# design.net
KiCad netlist of a schematic drawn in EasyEDA Pro
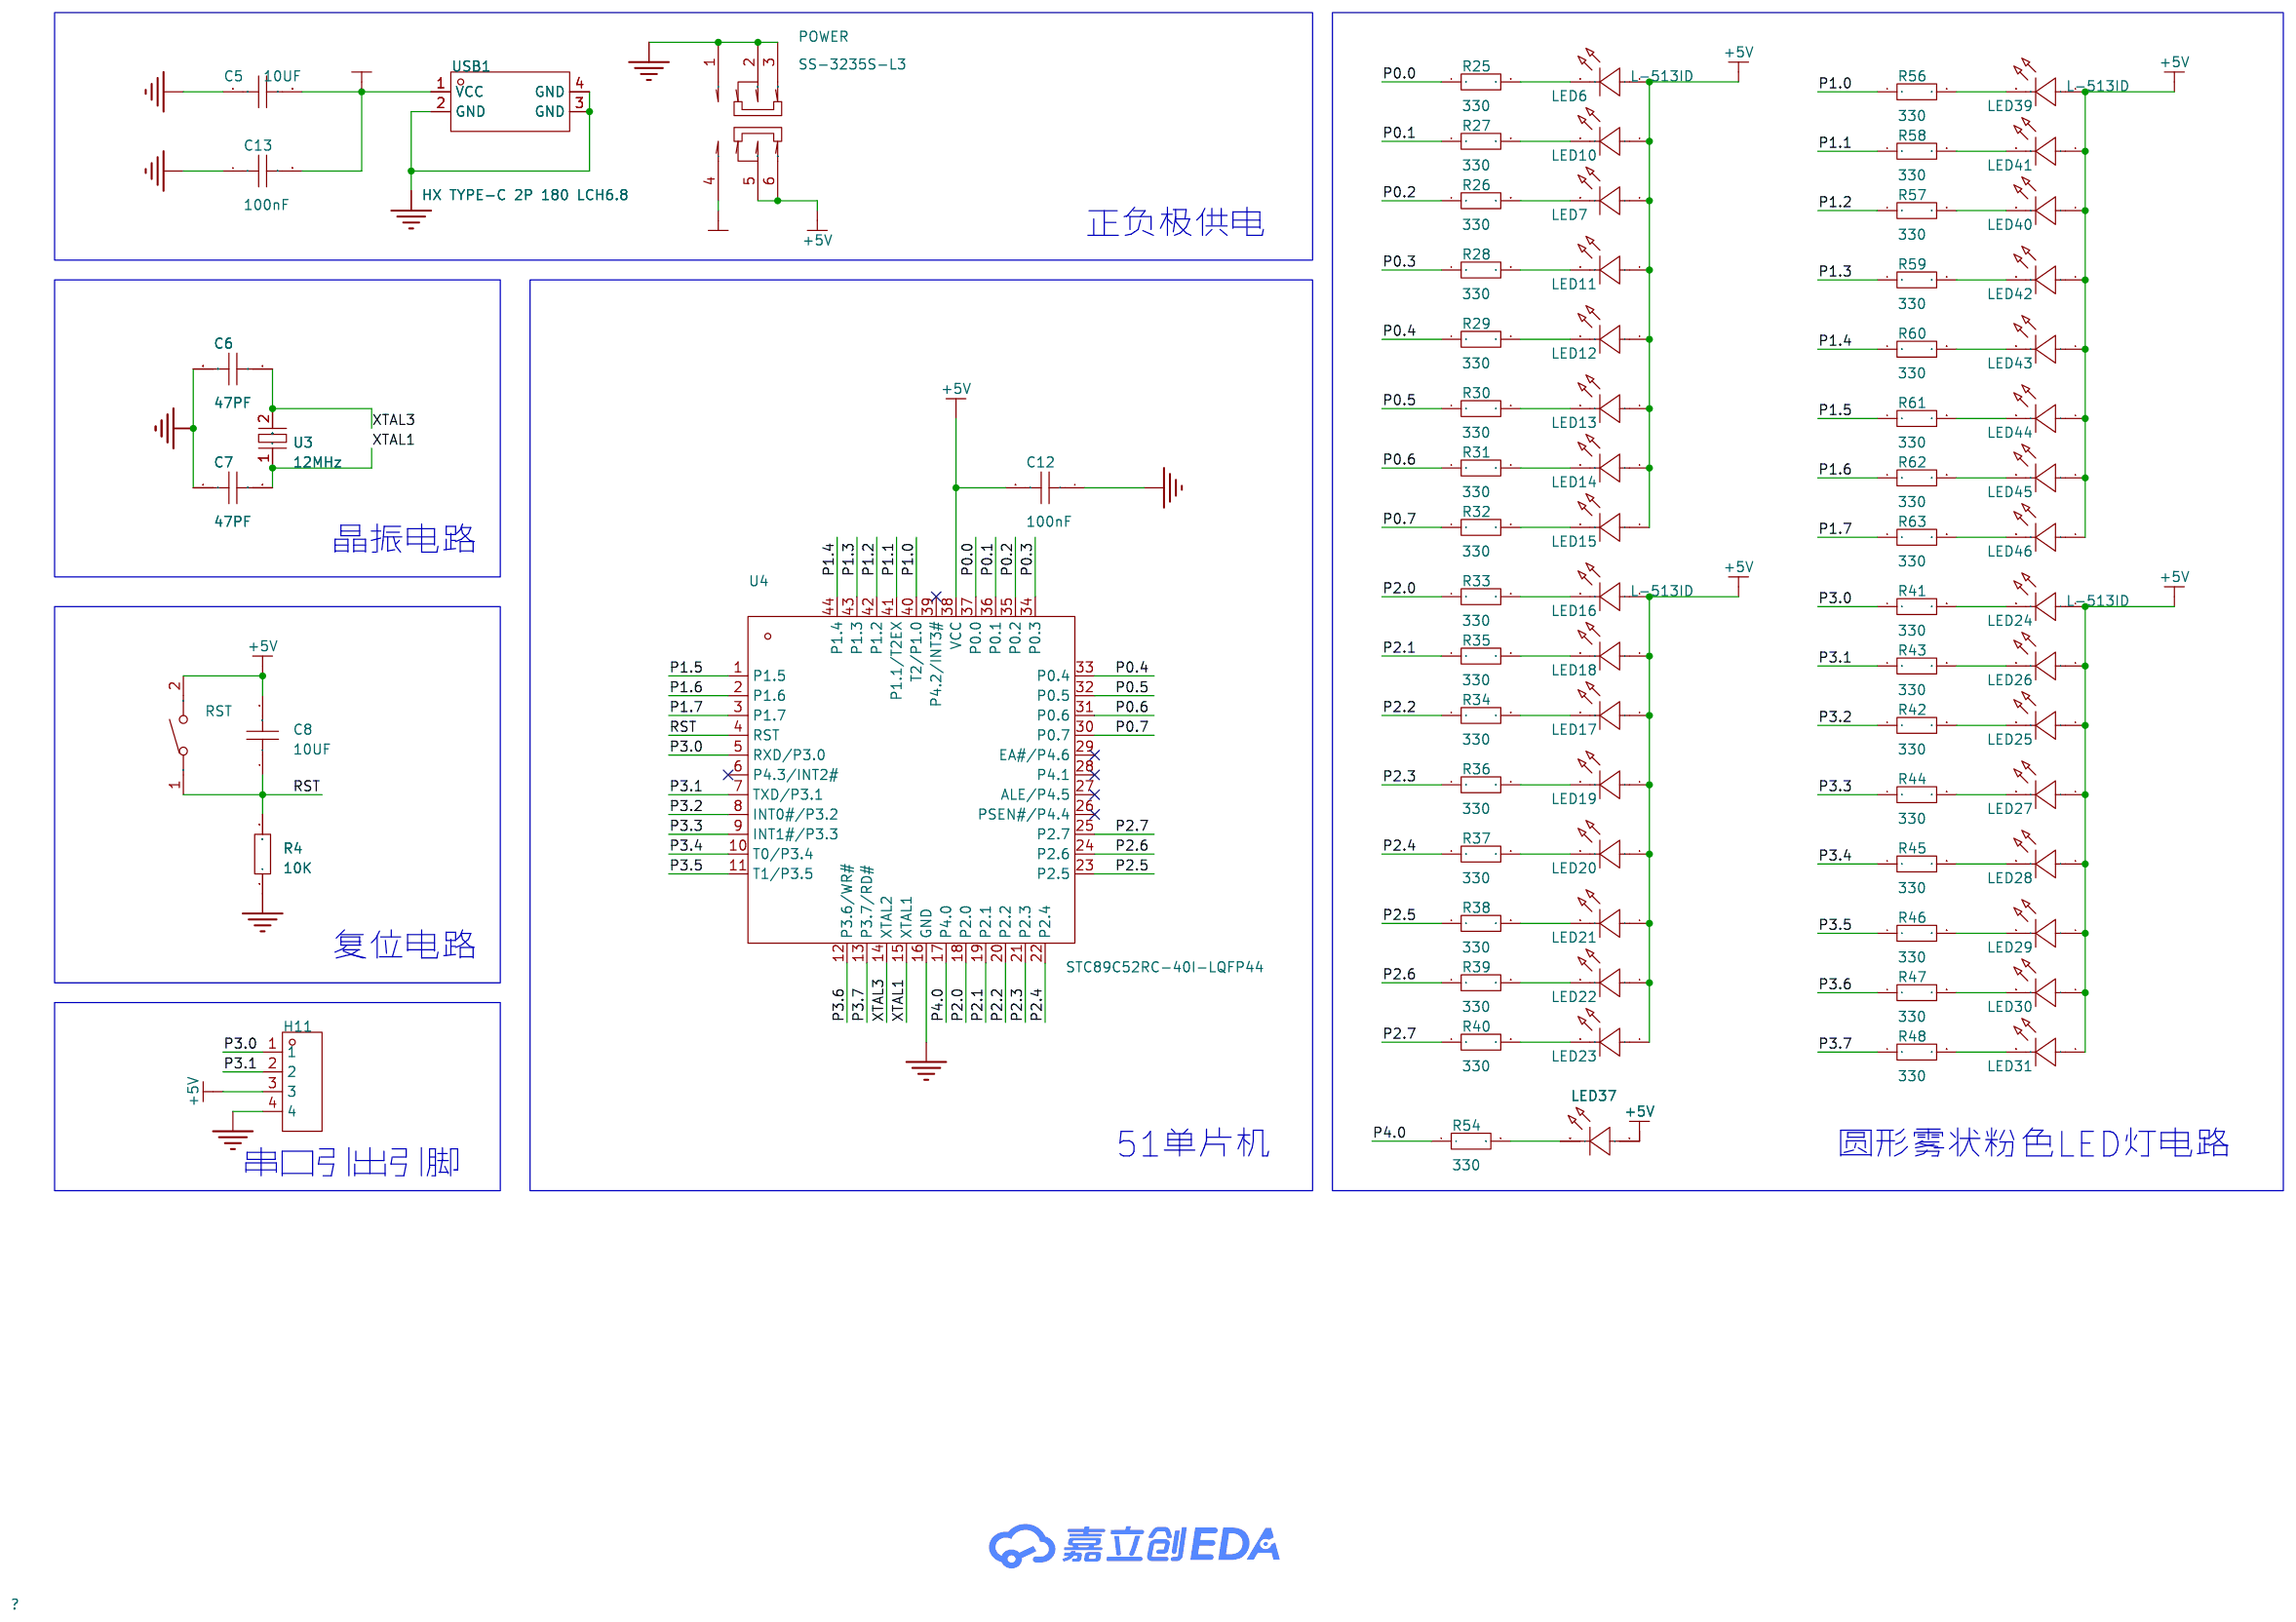
[diagram p0: schematic sheet]

(export (version "E")
  (design (tool "Eeschema 10.0.6"))
  (components
    (comp (ref "C5")
      (value "10UF")
      (footprint "easyedapro:C0805")
      (libsource (lib "easyedapro") (part "CapAcitance"))
    )
    (comp (ref "C6")
      (value "47PF")
      (footprint "easyedapro:C0805")
      (libsource (lib "easyedapro") (part "CapAcitance"))
    )
    (comp (ref "C7")
      (value "47PF")
      (footprint "easyedapro:C0805")
      (libsource (lib "easyedapro") (part "CapAcitance"))
    )
    (comp (ref "C8")
      (value "10UF")
      (footprint "easyedapro:C0805")
      (libsource (lib "easyedapro") (part "CapAcitance"))
    )
    (comp (ref "C12")
      (value "100nF")
      (footprint "easyedapro:C0805")
      (libsource (lib "easyedapro") (part "CapAcitance"))
    )
    (comp (ref "C13")
      (value "100nF")
      (footprint "easyedapro:C0805")
      (libsource (lib "easyedapro") (part "CapAcitance"))
    )
    (comp (ref "H11")
      (value "~")
      (footprint "easyedapro:HDR-TH_4P-P2.54-V-M")
      (libsource (lib "easyedapro") (part "PZ254V-11-04P"))
    )
    (comp (ref "LED6")
      (value "L-513ID")
      (footprint "easyedapro:LED-TH_BD5.9-P2.54-FD-1")
      (fields (field (name "Manufacturer") "PARALIGHT(光鼎)"))
      (libsource (lib "easyedapro") (part "L-513ID"))
    )
    (comp (ref "LED7")
      (value "L-513ID")
      (footprint "easyedapro:LED-TH_BD5.9-P2.54-FD-1")
      (fields (field (name "Manufacturer") "PARALIGHT(光鼎)"))
      (libsource (lib "easyedapro") (part "L-513ID"))
    )
    (comp (ref "LED10")
      (value "L-513ID")
      (footprint "easyedapro:LED-TH_BD5.9-P2.54-FD-1")
      (fields (field (name "Manufacturer") "PARALIGHT(光鼎)"))
      (libsource (lib "easyedapro") (part "L-513ID"))
    )
    (comp (ref "LED11")
      (value "L-513ID")
      (footprint "easyedapro:LED-TH_BD5.9-P2.54-FD-1")
      (fields (field (name "Manufacturer") "PARALIGHT(光鼎)"))
      (libsource (lib "easyedapro") (part "L-513ID"))
    )
    (comp (ref "LED12")
      (value "L-513ID")
      (footprint "easyedapro:LED-TH_BD5.9-P2.54-FD-1")
      (fields (field (name "Manufacturer") "PARALIGHT(光鼎)"))
      (libsource (lib "easyedapro") (part "L-513ID"))
    )
    (comp (ref "LED13")
      (value "L-513ID")
      (footprint "easyedapro:LED-TH_BD5.9-P2.54-FD-1")
      (fields (field (name "Manufacturer") "PARALIGHT(光鼎)"))
      (libsource (lib "easyedapro") (part "L-513ID"))
    )
    (comp (ref "LED14")
      (value "L-513ID")
      (footprint "easyedapro:LED-TH_BD5.9-P2.54-FD-1")
      (fields (field (name "Manufacturer") "PARALIGHT(光鼎)"))
      (libsource (lib "easyedapro") (part "L-513ID"))
    )
    (comp (ref "LED15")
      (value "L-513ID")
      (footprint "easyedapro:LED-TH_BD5.9-P2.54-FD-1")
      (fields (field (name "Manufacturer") "PARALIGHT(光鼎)"))
      (libsource (lib "easyedapro") (part "L-513ID"))
    )
    (comp (ref "LED16")
      (value "L-513ID")
      (footprint "easyedapro:LED-TH_BD5.9-P2.54-FD-1")
      (fields (field (name "Manufacturer") "PARALIGHT(光鼎)"))
      (libsource (lib "easyedapro") (part "L-513ID"))
    )
    (comp (ref "LED17")
      (value "L-513ID")
      (footprint "easyedapro:LED-TH_BD5.9-P2.54-FD-1")
      (fields (field (name "Manufacturer") "PARALIGHT(光鼎)"))
      (libsource (lib "easyedapro") (part "L-513ID"))
    )
    (comp (ref "LED18")
      (value "L-513ID")
      (footprint "easyedapro:LED-TH_BD5.9-P2.54-FD-1")
      (fields (field (name "Manufacturer") "PARALIGHT(光鼎)"))
      (libsource (lib "easyedapro") (part "L-513ID"))
    )
    (comp (ref "LED19")
      (value "L-513ID")
      (footprint "easyedapro:LED-TH_BD5.9-P2.54-FD-1")
      (fields (field (name "Manufacturer") "PARALIGHT(光鼎)"))
      (libsource (lib "easyedapro") (part "L-513ID"))
    )
    (comp (ref "LED20")
      (value "L-513ID")
      (footprint "easyedapro:LED-TH_BD5.9-P2.54-FD-1")
      (fields (field (name "Manufacturer") "PARALIGHT(光鼎)"))
      (libsource (lib "easyedapro") (part "L-513ID"))
    )
    (comp (ref "LED21")
      (value "L-513ID")
      (footprint "easyedapro:LED-TH_BD5.9-P2.54-FD-1")
      (fields (field (name "Manufacturer") "PARALIGHT(光鼎)"))
      (libsource (lib "easyedapro") (part "L-513ID"))
    )
    (comp (ref "LED22")
      (value "L-513ID")
      (footprint "easyedapro:LED-TH_BD5.9-P2.54-FD-1")
      (fields (field (name "Manufacturer") "PARALIGHT(光鼎)"))
      (libsource (lib "easyedapro") (part "L-513ID"))
    )
    (comp (ref "LED23")
      (value "L-513ID")
      (footprint "easyedapro:LED-TH_BD5.9-P2.54-FD-1")
      (fields (field (name "Manufacturer") "PARALIGHT(光鼎)"))
      (libsource (lib "easyedapro") (part "L-513ID"))
    )
    (comp (ref "LED24")
      (value "L-513ID")
      (footprint "easyedapro:LED-TH_BD5.9-P2.54-FD-1")
      (fields (field (name "Manufacturer") "PARALIGHT(光鼎)"))
      (libsource (lib "easyedapro") (part "L-513ID"))
    )
    (comp (ref "LED25")
      (value "L-513ID")
      (footprint "easyedapro:LED-TH_BD5.9-P2.54-FD-1")
      (fields (field (name "Manufacturer") "PARALIGHT(光鼎)"))
      (libsource (lib "easyedapro") (part "L-513ID"))
    )
    (comp (ref "LED26")
      (value "L-513ID")
      (footprint "easyedapro:LED-TH_BD5.9-P2.54-FD-1")
      (fields (field (name "Manufacturer") "PARALIGHT(光鼎)"))
      (libsource (lib "easyedapro") (part "L-513ID"))
    )
    (comp (ref "LED27")
      (value "L-513ID")
      (footprint "easyedapro:LED-TH_BD5.9-P2.54-FD-1")
      (fields (field (name "Manufacturer") "PARALIGHT(光鼎)"))
      (libsource (lib "easyedapro") (part "L-513ID"))
    )
    (comp (ref "LED28")
      (value "L-513ID")
      (footprint "easyedapro:LED-TH_BD5.9-P2.54-FD-1")
      (fields (field (name "Manufacturer") "PARALIGHT(光鼎)"))
      (libsource (lib "easyedapro") (part "L-513ID"))
    )
    (comp (ref "LED29")
      (value "L-513ID")
      (footprint "easyedapro:LED-TH_BD5.9-P2.54-FD-1")
      (fields (field (name "Manufacturer") "PARALIGHT(光鼎)"))
      (libsource (lib "easyedapro") (part "L-513ID"))
    )
    (comp (ref "LED30")
      (value "L-513ID")
      (footprint "easyedapro:LED-TH_BD5.9-P2.54-FD-1")
      (fields (field (name "Manufacturer") "PARALIGHT(光鼎)"))
      (libsource (lib "easyedapro") (part "L-513ID"))
    )
    (comp (ref "LED31")
      (value "L-513ID")
      (footprint "easyedapro:LED-TH_BD5.9-P2.54-FD-1")
      (fields (field (name "Manufacturer") "PARALIGHT(光鼎)"))
      (libsource (lib "easyedapro") (part "L-513ID"))
    )
    (comp (ref "LED37")
      (value "L-513ID")
      (footprint "easyedapro:LED-TH_BD5.9-P2.54-FD-1")
      (fields (field (name "Manufacturer") "PARALIGHT(光鼎)"))
      (libsource (lib "easyedapro") (part "L-513ID"))
    )
    (comp (ref "LED39")
      (value "L-513ID")
      (footprint "easyedapro:LED-TH_BD5.9-P2.54-FD-1")
      (fields (field (name "Manufacturer") "PARALIGHT(光鼎)"))
      (libsource (lib "easyedapro") (part "L-513ID"))
    )
    (comp (ref "LED40")
      (value "L-513ID")
      (footprint "easyedapro:LED-TH_BD5.9-P2.54-FD-1")
      (fields (field (name "Manufacturer") "PARALIGHT(光鼎)"))
      (libsource (lib "easyedapro") (part "L-513ID"))
    )
    (comp (ref "LED41")
      (value "L-513ID")
      (footprint "easyedapro:LED-TH_BD5.9-P2.54-FD-1")
      (fields (field (name "Manufacturer") "PARALIGHT(光鼎)"))
      (libsource (lib "easyedapro") (part "L-513ID"))
    )
    (comp (ref "LED42")
      (value "L-513ID")
      (footprint "easyedapro:LED-TH_BD5.9-P2.54-FD-1")
      (fields (field (name "Manufacturer") "PARALIGHT(光鼎)"))
      (libsource (lib "easyedapro") (part "L-513ID"))
    )
    (comp (ref "LED43")
      (value "L-513ID")
      (footprint "easyedapro:LED-TH_BD5.9-P2.54-FD-1")
      (fields (field (name "Manufacturer") "PARALIGHT(光鼎)"))
      (libsource (lib "easyedapro") (part "L-513ID"))
    )
    (comp (ref "LED44")
      (value "L-513ID")
      (footprint "easyedapro:LED-TH_BD5.9-P2.54-FD-1")
      (fields (field (name "Manufacturer") "PARALIGHT(光鼎)"))
      (libsource (lib "easyedapro") (part "L-513ID"))
    )
    (comp (ref "LED45")
      (value "L-513ID")
      (footprint "easyedapro:LED-TH_BD5.9-P2.54-FD-1")
      (fields (field (name "Manufacturer") "PARALIGHT(光鼎)"))
      (libsource (lib "easyedapro") (part "L-513ID"))
    )
    (comp (ref "LED46")
      (value "L-513ID")
      (footprint "easyedapro:LED-TH_BD5.9-P2.54-FD-1")
      (fields (field (name "Manufacturer") "PARALIGHT(光鼎)"))
      (libsource (lib "easyedapro") (part "L-513ID"))
    )
    (comp (ref "POWER")
      (value "SS-3235S-L3")
      (footprint "easyedapro:SW-SMD_SS-3235S-L3.00")
      (description "电路结构:双刀双掷;安装方式:立贴;开关颜色:黑色;额定电流(DC):50mA;额定电压(DC):12V;额定电流(AC):50mA;额定电压(AC):12V;机械寿命:1万次;")
      (fields (field (name "Manufacturer") "XKB Connectivity(中国星坤)"))
      (libsource (lib "easyedapro") (part "SS-3235S-L3"))
    )
    (comp (ref "R4") (value "10K") (footprint "easyedapro:R0805") (libsource (lib "easyedapro") (part "电阻")))
    (comp (ref "R25") (value "330") (footprint "easyedapro:R0805") (libsource (lib "easyedapro") (part "电阻")))
    (comp (ref "R26") (value "330") (footprint "easyedapro:R0805") (libsource (lib "easyedapro") (part "电阻")))
    (comp (ref "R27") (value "330") (footprint "easyedapro:R0805") (libsource (lib "easyedapro") (part "电阻")))
    (comp (ref "R28") (value "330") (footprint "easyedapro:R0805") (libsource (lib "easyedapro") (part "电阻")))
    (comp (ref "R29") (value "330") (footprint "easyedapro:R0805") (libsource (lib "easyedapro") (part "电阻")))
    (comp (ref "R30") (value "330") (footprint "easyedapro:R0805") (libsource (lib "easyedapro") (part "电阻")))
    (comp (ref "R31") (value "330") (footprint "easyedapro:R0805") (libsource (lib "easyedapro") (part "电阻")))
    (comp (ref "R32") (value "330") (footprint "easyedapro:R0805") (libsource (lib "easyedapro") (part "电阻")))
    (comp (ref "R33") (value "330") (footprint "easyedapro:R0805") (libsource (lib "easyedapro") (part "电阻")))
    (comp (ref "R34") (value "330") (footprint "easyedapro:R0805") (libsource (lib "easyedapro") (part "电阻")))
    (comp (ref "R35") (value "330") (footprint "easyedapro:R0805") (libsource (lib "easyedapro") (part "电阻")))
    (comp (ref "R36") (value "330") (footprint "easyedapro:R0805") (libsource (lib "easyedapro") (part "电阻")))
    (comp (ref "R37") (value "330") (footprint "easyedapro:R0805") (libsource (lib "easyedapro") (part "电阻")))
    (comp (ref "R38") (value "330") (footprint "easyedapro:R0805") (libsource (lib "easyedapro") (part "电阻")))
    (comp (ref "R39") (value "330") (footprint "easyedapro:R0805") (libsource (lib "easyedapro") (part "电阻")))
    (comp (ref "R40") (value "330") (footprint "easyedapro:R0805") (libsource (lib "easyedapro") (part "电阻")))
    (comp (ref "R41") (value "330") (footprint "easyedapro:R0805") (libsource (lib "easyedapro") (part "电阻")))
    (comp (ref "R42") (value "330") (footprint "easyedapro:R0805") (libsource (lib "easyedapro") (part "电阻")))
    (comp (ref "R43") (value "330") (footprint "easyedapro:R0805") (libsource (lib "easyedapro") (part "电阻")))
    (comp (ref "R44") (value "330") (footprint "easyedapro:R0805") (libsource (lib "easyedapro") (part "电阻")))
    (comp (ref "R45") (value "330") (footprint "easyedapro:R0805") (libsource (lib "easyedapro") (part "电阻")))
    (comp (ref "R46") (value "330") (footprint "easyedapro:R0805") (libsource (lib "easyedapro") (part "电阻")))
    (comp (ref "R47") (value "330") (footprint "easyedapro:R0805") (libsource (lib "easyedapro") (part "电阻")))
    (comp (ref "R48") (value "330") (footprint "easyedapro:R0805") (libsource (lib "easyedapro") (part "电阻")))
    (comp (ref "R54") (value "330") (footprint "easyedapro:R0805") (libsource (lib "easyedapro") (part "电阻")))
    (comp (ref "R56") (value "330") (footprint "easyedapro:R0805") (libsource (lib "easyedapro") (part "电阻")))
    (comp (ref "R57") (value "330") (footprint "easyedapro:R0805") (libsource (lib "easyedapro") (part "电阻")))
    (comp (ref "R58") (value "330") (footprint "easyedapro:R0805") (libsource (lib "easyedapro") (part "电阻")))
    (comp (ref "R59") (value "330") (footprint "easyedapro:R0805") (libsource (lib "easyedapro") (part "电阻")))
    (comp (ref "R60") (value "330") (footprint "easyedapro:R0805") (libsource (lib "easyedapro") (part "电阻")))
    (comp (ref "R61") (value "330") (footprint "easyedapro:R0805") (libsource (lib "easyedapro") (part "电阻")))
    (comp (ref "R62") (value "330") (footprint "easyedapro:R0805") (libsource (lib "easyedapro") (part "电阻")))
    (comp (ref "R63") (value "330") (footprint "easyedapro:R0805") (libsource (lib "easyedapro") (part "电阻")))
    (comp (ref "RST")
      (value "轻触按键3*4*H")
      (footprint "easyedapro:SW-SMD_L4.0-W2.9-LS5.0")
      (libsource (lib "easyedapro") (part "轻触按键3*4*H"))
    )
    (comp (ref "U3")
      (value "12MHz")
      (footprint "easyedapro:CRYSTAL-SMD_L11.4-W4.7-LS12.7")
      (description "频率:12MHz;常温频差:±30ppm;外接负载电容:18pF;频率稳定度(全温):±35ppm;")
      (fields
        (field (name "Manufacturer Part") "ABLS-12.000MHZ-B4H-T")
        (field (name "Manufacturer") "ABRACON")
      )
      (libsource (lib "easyedapro") (part "ABLS-12.000MHZ-B4H-T"))
    )
    (comp (ref "U4")
      (value "STC89C52RC-40I-LQFP44")
      (footprint "easyedapro:LQFP-44_L10.0-W10.0-P0.80-LS12.0-BL")
      (description "CPU内核:51系列;应用领域:-;")
      (fields (field (name "Manufacturer") "STC"))
      (libsource (lib "easyedapro") (part "STC89C52RC-40I_C8707"))
    )
    (comp (ref "USB1")
      (value "HX TYPE-C 2P 180 LCH6.8")
      (footprint "easyedapro:USB-TH_HX-TYPE-C-2P-180-LCH6.8")
      (description "连接器类型:Type-C;标准:-;公母:母;安装方式:直插;触点数量:2P;端口数量:1;额定电流 - 电源:3A;工作温度范围:-30°C~+80°C;")
      (fields (field (name "Manufacturer") "hanxia(韩下)"))
      (libsource (lib "easyedapro") (part "HX TYPE-C 2P 180 LCH6.8"))
    )
  )
  (nets
    (net (code "1") (name "+5V") (class "Default")
      (node (ref "C12") (pin "2") (pinfunction "2_2") (pintype "input"))
      (node (ref "C8") (pin "2") (pinfunction "2_2") (pintype "input"))
      (node (ref "H11") (pin "3") (pinfunction "3_3") (pintype "unspecified"))
      (node (ref "LED10") (pin "1") (pinfunction "A_1") (pintype "unspecified"))
      (node (ref "LED11") (pin "1") (pinfunction "A_1") (pintype "unspecified"))
      (node (ref "LED12") (pin "1") (pinfunction "A_1") (pintype "unspecified"))
      (node (ref "LED13") (pin "1") (pinfunction "A_1") (pintype "unspecified"))
      (node (ref "LED14") (pin "1") (pinfunction "A_1") (pintype "unspecified"))
      (node (ref "LED15") (pin "1") (pinfunction "A_1") (pintype "unspecified"))
      (node (ref "LED16") (pin "1") (pinfunction "A_1") (pintype "unspecified"))
      (node (ref "LED17") (pin "1") (pinfunction "A_1") (pintype "unspecified"))
      (node (ref "LED18") (pin "1") (pinfunction "A_1") (pintype "unspecified"))
      (node (ref "LED19") (pin "1") (pinfunction "A_1") (pintype "unspecified"))
      (node (ref "LED20") (pin "1") (pinfunction "A_1") (pintype "unspecified"))
      (node (ref "LED21") (pin "1") (pinfunction "A_1") (pintype "unspecified"))
      (node (ref "LED22") (pin "1") (pinfunction "A_1") (pintype "unspecified"))
      (node (ref "LED23") (pin "1") (pinfunction "A_1") (pintype "unspecified"))
      (node (ref "LED24") (pin "1") (pinfunction "A_1") (pintype "unspecified"))
      (node (ref "LED25") (pin "1") (pinfunction "A_1") (pintype "unspecified"))
      (node (ref "LED26") (pin "1") (pinfunction "A_1") (pintype "unspecified"))
      (node (ref "LED27") (pin "1") (pinfunction "A_1") (pintype "unspecified"))
      (node (ref "LED28") (pin "1") (pinfunction "A_1") (pintype "unspecified"))
      (node (ref "LED29") (pin "1") (pinfunction "A_1") (pintype "unspecified"))
      (node (ref "LED30") (pin "1") (pinfunction "A_1") (pintype "unspecified"))
      (node (ref "LED31") (pin "1") (pinfunction "A_1") (pintype "unspecified"))
      (node (ref "LED37") (pin "1") (pinfunction "A_1") (pintype "unspecified"))
      (node (ref "LED39") (pin "1") (pinfunction "A_1") (pintype "unspecified"))
      (node (ref "LED40") (pin "1") (pinfunction "A_1") (pintype "unspecified"))
      (node (ref "LED41") (pin "1") (pinfunction "A_1") (pintype "unspecified"))
      (node (ref "LED42") (pin "1") (pinfunction "A_1") (pintype "unspecified"))
      (node (ref "LED43") (pin "1") (pinfunction "A_1") (pintype "unspecified"))
      (node (ref "LED44") (pin "1") (pinfunction "A_1") (pintype "unspecified"))
      (node (ref "LED45") (pin "1") (pinfunction "A_1") (pintype "unspecified"))
      (node (ref "LED46") (pin "1") (pinfunction "A_1") (pintype "unspecified"))
      (node (ref "LED6") (pin "1") (pinfunction "A_1") (pintype "unspecified"))
      (node (ref "LED7") (pin "1") (pinfunction "A_1") (pintype "unspecified"))
      (node (ref "POWER") (pin "5") (pinfunction "5_5") (pintype "unspecified"))
      (node (ref "POWER") (pin "6") (pinfunction "6_6") (pintype "unspecified"))
      (node (ref "RST") (pin "2") (pinfunction "2_2") (pintype "unspecified"))
      (node (ref "U4") (pin "38") (pinfunction "VCC_38") (pintype "unspecified"))
    )
    (net (code "2") (name "/P0.0") (class "Default")
      (node (ref "R25") (pin "1") (pinfunction "1_1") (pintype "input"))
      (node (ref "U4") (pin "37") (pinfunction "P0.0_37") (pintype "unspecified"))
    )
    (net (code "3") (name "/P0.1") (class "Default")
      (node (ref "R27") (pin "1") (pinfunction "1_1") (pintype "input"))
      (node (ref "U4") (pin "36") (pinfunction "P0.1_36") (pintype "unspecified"))
    )
    (net (code "4") (name "/P0.2") (class "Default")
      (node (ref "R26") (pin "1") (pinfunction "1_1") (pintype "input"))
      (node (ref "U4") (pin "35") (pinfunction "P0.2_35") (pintype "unspecified"))
    )
    (net (code "5") (name "/P0.3") (class "Default")
      (node (ref "R28") (pin "1") (pinfunction "1_1") (pintype "input"))
      (node (ref "U4") (pin "34") (pinfunction "P0.3_34") (pintype "unspecified"))
    )
    (net (code "6") (name "/P0.4") (class "Default")
      (node (ref "R29") (pin "1") (pinfunction "1_1") (pintype "input"))
      (node (ref "U4") (pin "33") (pinfunction "P0.4_33") (pintype "unspecified"))
    )
    (net (code "7") (name "/P0.5") (class "Default")
      (node (ref "R30") (pin "1") (pinfunction "1_1") (pintype "input"))
      (node (ref "U4") (pin "32") (pinfunction "P0.5_32") (pintype "unspecified"))
    )
    (net (code "8") (name "/P0.6") (class "Default")
      (node (ref "R31") (pin "1") (pinfunction "1_1") (pintype "input"))
      (node (ref "U4") (pin "31") (pinfunction "P0.6_31") (pintype "unspecified"))
    )
    (net (code "9") (name "/P0.7") (class "Default")
      (node (ref "R32") (pin "1") (pinfunction "1_1") (pintype "input"))
      (node (ref "U4") (pin "30") (pinfunction "P0.7_30") (pintype "unspecified"))
    )
    (net (code "10") (name "/P1.0") (class "Default")
      (node (ref "R56") (pin "1") (pinfunction "1_1") (pintype "input"))
      (node (ref "U4") (pin "40") (pinfunction "T2/P1.0_40") (pintype "unspecified"))
    )
    (net (code "11") (name "/P1.1") (class "Default")
      (node (ref "R58") (pin "1") (pinfunction "1_1") (pintype "input"))
      (node (ref "U4") (pin "41") (pinfunction "P1.1/T2EX_41") (pintype "unspecified"))
    )
    (net (code "12") (name "/P1.2") (class "Default")
      (node (ref "R57") (pin "1") (pinfunction "1_1") (pintype "input"))
      (node (ref "U4") (pin "42") (pinfunction "P1.2_42") (pintype "unspecified"))
    )
    (net (code "13") (name "/P1.3") (class "Default")
      (node (ref "R59") (pin "1") (pinfunction "1_1") (pintype "input"))
      (node (ref "U4") (pin "43") (pinfunction "P1.3_43") (pintype "unspecified"))
    )
    (net (code "14") (name "/P1.4") (class "Default")
      (node (ref "R60") (pin "1") (pinfunction "1_1") (pintype "input"))
      (node (ref "U4") (pin "44") (pinfunction "P1.4_44") (pintype "unspecified"))
    )
    (net (code "15") (name "/P1.5") (class "Default")
      (node (ref "R61") (pin "1") (pinfunction "1_1") (pintype "input"))
      (node (ref "U4") (pin "1") (pinfunction "P1.5_1") (pintype "unspecified"))
    )
    (net (code "16") (name "/P1.6") (class "Default")
      (node (ref "R62") (pin "1") (pinfunction "1_1") (pintype "input"))
      (node (ref "U4") (pin "2") (pinfunction "P1.6_2") (pintype "unspecified"))
    )
    (net (code "17") (name "/P1.7") (class "Default")
      (node (ref "R63") (pin "1") (pinfunction "1_1") (pintype "input"))
      (node (ref "U4") (pin "3") (pinfunction "P1.7_3") (pintype "unspecified"))
    )
    (net (code "18") (name "/P2.0") (class "Default")
      (node (ref "R33") (pin "1") (pinfunction "1_1") (pintype "input"))
      (node (ref "U4") (pin "18") (pinfunction "P2.0_18") (pintype "unspecified"))
    )
    (net (code "19") (name "/P2.1") (class "Default")
      (node (ref "R35") (pin "1") (pinfunction "1_1") (pintype "input"))
      (node (ref "U4") (pin "19") (pinfunction "P2.1_19") (pintype "unspecified"))
    )
    (net (code "20") (name "/P2.2") (class "Default")
      (node (ref "R34") (pin "1") (pinfunction "1_1") (pintype "input"))
      (node (ref "U4") (pin "20") (pinfunction "P2.2_20") (pintype "unspecified"))
    )
    (net (code "21") (name "/P2.3") (class "Default")
      (node (ref "R36") (pin "1") (pinfunction "1_1") (pintype "input"))
      (node (ref "U4") (pin "21") (pinfunction "P2.3_21") (pintype "unspecified"))
    )
    (net (code "22") (name "/P2.4") (class "Default")
      (node (ref "R37") (pin "1") (pinfunction "1_1") (pintype "input"))
      (node (ref "U4") (pin "22") (pinfunction "P2.4_22") (pintype "unspecified"))
    )
    (net (code "23") (name "/P2.5") (class "Default")
      (node (ref "R38") (pin "1") (pinfunction "1_1") (pintype "input"))
      (node (ref "U4") (pin "23") (pinfunction "P2.5_23") (pintype "unspecified"))
    )
    (net (code "24") (name "/P2.6") (class "Default")
      (node (ref "R39") (pin "1") (pinfunction "1_1") (pintype "input"))
      (node (ref "U4") (pin "24") (pinfunction "P2.6_24") (pintype "unspecified"))
    )
    (net (code "25") (name "/P2.7") (class "Default")
      (node (ref "R40") (pin "1") (pinfunction "1_1") (pintype "input"))
      (node (ref "U4") (pin "25") (pinfunction "P2.7_25") (pintype "unspecified"))
    )
    (net (code "26") (name "/P3.0") (class "Default")
      (node (ref "H11") (pin "1") (pinfunction "1_1") (pintype "unspecified"))
      (node (ref "R41") (pin "1") (pinfunction "1_1") (pintype "input"))
      (node (ref "U4") (pin "5") (pinfunction "RXD/P3.0_5") (pintype "unspecified"))
    )
    (net (code "27") (name "/P3.1") (class "Default")
      (node (ref "H11") (pin "2") (pinfunction "2_2") (pintype "unspecified"))
      (node (ref "R43") (pin "1") (pinfunction "1_1") (pintype "input"))
      (node (ref "U4") (pin "7") (pinfunction "TXD/P3.1_7") (pintype "unspecified"))
    )
    (net (code "28") (name "/P3.2") (class "Default")
      (node (ref "R42") (pin "1") (pinfunction "1_1") (pintype "input"))
      (node (ref "U4") (pin "8") (pinfunction "INT0#/P3.2_8") (pintype "unspecified"))
    )
    (net (code "29") (name "/P3.3") (class "Default")
      (node (ref "R44") (pin "1") (pinfunction "1_1") (pintype "input"))
      (node (ref "U4") (pin "9") (pinfunction "INT1#/P3.3_9") (pintype "unspecified"))
    )
    (net (code "30") (name "/P3.4") (class "Default")
      (node (ref "R45") (pin "1") (pinfunction "1_1") (pintype "input"))
      (node (ref "U4") (pin "10") (pinfunction "T0/P3.4_10") (pintype "unspecified"))
    )
    (net (code "31") (name "/P3.5") (class "Default")
      (node (ref "R46") (pin "1") (pinfunction "1_1") (pintype "input"))
      (node (ref "U4") (pin "11") (pinfunction "T1/P3.5_11") (pintype "unspecified"))
    )
    (net (code "32") (name "/P3.6") (class "Default")
      (node (ref "R47") (pin "1") (pinfunction "1_1") (pintype "input"))
      (node (ref "U4") (pin "12") (pinfunction "P3.6/WR#_12") (pintype "unspecified"))
    )
    (net (code "33") (name "/P3.7") (class "Default")
      (node (ref "R48") (pin "1") (pinfunction "1_1") (pintype "input"))
      (node (ref "U4") (pin "13") (pinfunction "P3.7/RD#_13") (pintype "unspecified"))
    )
    (net (code "34") (name "/P4.0") (class "Default")
      (node (ref "R54") (pin "1") (pinfunction "1_1") (pintype "input"))
      (node (ref "U4") (pin "17") (pinfunction "P4.0_17") (pintype "unspecified"))
    )
    (net (code "35") (name "/RST") (class "Default")
      (node (ref "C8") (pin "1") (pinfunction "1_1") (pintype "input"))
      (node (ref "R4") (pin "2") (pinfunction "2_2") (pintype "input"))
      (node (ref "RST") (pin "1") (pinfunction "1_1") (pintype "unspecified"))
      (node (ref "U4") (pin "4") (pinfunction "RST_4") (pintype "unspecified"))
    )
    (net (code "36") (name "/XTAL1") (class "Default")
      (node (ref "C7") (pin "2") (pinfunction "2_2") (pintype "input"))
      (node (ref "U3") (pin "1") (pinfunction "1_1") (pintype "input"))
      (node (ref "U4") (pin "15") (pinfunction "XTAL1_15") (pintype "unspecified"))
    )
    (net (code "37") (name "/XTAL3") (class "Default")
      (node (ref "C6") (pin "1") (pinfunction "1_1") (pintype "input"))
      (node (ref "U3") (pin "2") (pinfunction "GND_2") (pintype "input"))
      (node (ref "U4") (pin "14") (pinfunction "XTAL2_14") (pintype "unspecified"))
    )
    (net (code "38") (name "GND") (class "Default")
      (node (ref "C12") (pin "1") (pinfunction "1_1") (pintype "input"))
      (node (ref "C13") (pin "1") (pinfunction "1_1") (pintype "input"))
      (node (ref "C5") (pin "1") (pinfunction "1_1") (pintype "input"))
      (node (ref "C6") (pin "2") (pinfunction "2_2") (pintype "input"))
      (node (ref "C7") (pin "1") (pinfunction "1_1") (pintype "input"))
      (node (ref "H11") (pin "4") (pinfunction "4_4") (pintype "unspecified"))
      (node (ref "POWER") (pin "1") (pinfunction "1_1") (pintype "unspecified"))
      (node (ref "POWER") (pin "2") (pinfunction "2_2") (pintype "unspecified"))
      (node (ref "POWER") (pin "3") (pinfunction "3_3") (pintype "unspecified"))
      (node (ref "R4") (pin "1") (pinfunction "1_1") (pintype "input"))
      (node (ref "U4") (pin "16") (pinfunction "GND_16") (pintype "unspecified"))
      (node (ref "USB1") (pin "2") (pinfunction "GND_2") (pintype "unspecified"))
      (node (ref "USB1") (pin "3") (pinfunction "GND_3") (pintype "unspecified"))
      (node (ref "USB1") (pin "4") (pinfunction "GND_4") (pintype "unspecified"))
    )
    (net (code "39") (name "Net-(LED6-K)") (class "Default")
      (node (ref "LED6") (pin "2") (pinfunction "K_2") (pintype "unspecified"))
      (node (ref "R25") (pin "2") (pinfunction "2_2") (pintype "input"))
    )
    (net (code "40") (name "Net-(LED7-K)") (class "Default")
      (node (ref "LED7") (pin "2") (pinfunction "K_2") (pintype "unspecified"))
      (node (ref "R26") (pin "2") (pinfunction "2_2") (pintype "input"))
    )
    (net (code "41") (name "Net-(LED10-K)") (class "Default")
      (node (ref "LED10") (pin "2") (pinfunction "K_2") (pintype "unspecified"))
      (node (ref "R27") (pin "2") (pinfunction "2_2") (pintype "input"))
    )
    (net (code "42") (name "Net-(LED11-K)") (class "Default")
      (node (ref "LED11") (pin "2") (pinfunction "K_2") (pintype "unspecified"))
      (node (ref "R28") (pin "2") (pinfunction "2_2") (pintype "input"))
    )
    (net (code "43") (name "Net-(LED12-K)") (class "Default")
      (node (ref "LED12") (pin "2") (pinfunction "K_2") (pintype "unspecified"))
      (node (ref "R29") (pin "2") (pinfunction "2_2") (pintype "input"))
    )
    (net (code "44") (name "Net-(LED13-K)") (class "Default")
      (node (ref "LED13") (pin "2") (pinfunction "K_2") (pintype "unspecified"))
      (node (ref "R30") (pin "2") (pinfunction "2_2") (pintype "input"))
    )
    (net (code "45") (name "Net-(LED14-K)") (class "Default")
      (node (ref "LED14") (pin "2") (pinfunction "K_2") (pintype "unspecified"))
      (node (ref "R31") (pin "2") (pinfunction "2_2") (pintype "input"))
    )
    (net (code "46") (name "Net-(LED15-K)") (class "Default")
      (node (ref "LED15") (pin "2") (pinfunction "K_2") (pintype "unspecified"))
      (node (ref "R32") (pin "2") (pinfunction "2_2") (pintype "input"))
    )
    (net (code "47") (name "Net-(LED16-K)") (class "Default")
      (node (ref "LED16") (pin "2") (pinfunction "K_2") (pintype "unspecified"))
      (node (ref "R33") (pin "2") (pinfunction "2_2") (pintype "input"))
    )
    (net (code "48") (name "Net-(LED17-K)") (class "Default")
      (node (ref "LED17") (pin "2") (pinfunction "K_2") (pintype "unspecified"))
      (node (ref "R34") (pin "2") (pinfunction "2_2") (pintype "input"))
    )
    (net (code "49") (name "Net-(LED18-K)") (class "Default")
      (node (ref "LED18") (pin "2") (pinfunction "K_2") (pintype "unspecified"))
      (node (ref "R35") (pin "2") (pinfunction "2_2") (pintype "input"))
    )
    (net (code "50") (name "Net-(LED19-K)") (class "Default")
      (node (ref "LED19") (pin "2") (pinfunction "K_2") (pintype "unspecified"))
      (node (ref "R36") (pin "2") (pinfunction "2_2") (pintype "input"))
    )
    (net (code "51") (name "Net-(LED20-K)") (class "Default")
      (node (ref "LED20") (pin "2") (pinfunction "K_2") (pintype "unspecified"))
      (node (ref "R37") (pin "2") (pinfunction "2_2") (pintype "input"))
    )
    (net (code "52") (name "Net-(LED21-K)") (class "Default")
      (node (ref "LED21") (pin "2") (pinfunction "K_2") (pintype "unspecified"))
      (node (ref "R38") (pin "2") (pinfunction "2_2") (pintype "input"))
    )
    (net (code "53") (name "Net-(LED22-K)") (class "Default")
      (node (ref "LED22") (pin "2") (pinfunction "K_2") (pintype "unspecified"))
      (node (ref "R39") (pin "2") (pinfunction "2_2") (pintype "input"))
    )
    (net (code "54") (name "Net-(LED23-K)") (class "Default")
      (node (ref "LED23") (pin "2") (pinfunction "K_2") (pintype "unspecified"))
      (node (ref "R40") (pin "2") (pinfunction "2_2") (pintype "input"))
    )
    (net (code "55") (name "Net-(LED24-K)") (class "Default")
      (node (ref "LED24") (pin "2") (pinfunction "K_2") (pintype "unspecified"))
      (node (ref "R41") (pin "2") (pinfunction "2_2") (pintype "input"))
    )
    (net (code "56") (name "Net-(LED25-K)") (class "Default")
      (node (ref "LED25") (pin "2") (pinfunction "K_2") (pintype "unspecified"))
      (node (ref "R42") (pin "2") (pinfunction "2_2") (pintype "input"))
    )
    (net (code "57") (name "Net-(LED26-K)") (class "Default")
      (node (ref "LED26") (pin "2") (pinfunction "K_2") (pintype "unspecified"))
      (node (ref "R43") (pin "2") (pinfunction "2_2") (pintype "input"))
    )
    (net (code "58") (name "Net-(LED27-K)") (class "Default")
      (node (ref "LED27") (pin "2") (pinfunction "K_2") (pintype "unspecified"))
      (node (ref "R44") (pin "2") (pinfunction "2_2") (pintype "input"))
    )
    (net (code "59") (name "Net-(LED28-K)") (class "Default")
      (node (ref "LED28") (pin "2") (pinfunction "K_2") (pintype "unspecified"))
      (node (ref "R45") (pin "2") (pinfunction "2_2") (pintype "input"))
    )
    (net (code "60") (name "Net-(LED29-K)") (class "Default")
      (node (ref "LED29") (pin "2") (pinfunction "K_2") (pintype "unspecified"))
      (node (ref "R46") (pin "2") (pinfunction "2_2") (pintype "input"))
    )
    (net (code "61") (name "Net-(LED30-K)") (class "Default")
      (node (ref "LED30") (pin "2") (pinfunction "K_2") (pintype "unspecified"))
      (node (ref "R47") (pin "2") (pinfunction "2_2") (pintype "input"))
    )
    (net (code "62") (name "Net-(LED31-K)") (class "Default")
      (node (ref "LED31") (pin "2") (pinfunction "K_2") (pintype "unspecified"))
      (node (ref "R48") (pin "2") (pinfunction "2_2") (pintype "input"))
    )
    (net (code "63") (name "Net-(LED37-K)") (class "Default")
      (node (ref "LED37") (pin "2") (pinfunction "K_2") (pintype "unspecified"))
      (node (ref "R54") (pin "2") (pinfunction "2_2") (pintype "input"))
    )
    (net (code "64") (name "Net-(LED39-K)") (class "Default")
      (node (ref "LED39") (pin "2") (pinfunction "K_2") (pintype "unspecified"))
      (node (ref "R56") (pin "2") (pinfunction "2_2") (pintype "input"))
    )
    (net (code "65") (name "Net-(LED40-K)") (class "Default")
      (node (ref "LED40") (pin "2") (pinfunction "K_2") (pintype "unspecified"))
      (node (ref "R57") (pin "2") (pinfunction "2_2") (pintype "input"))
    )
    (net (code "66") (name "Net-(LED41-K)") (class "Default")
      (node (ref "LED41") (pin "2") (pinfunction "K_2") (pintype "unspecified"))
      (node (ref "R58") (pin "2") (pinfunction "2_2") (pintype "input"))
    )
    (net (code "67") (name "Net-(LED42-K)") (class "Default")
      (node (ref "LED42") (pin "2") (pinfunction "K_2") (pintype "unspecified"))
      (node (ref "R59") (pin "2") (pinfunction "2_2") (pintype "input"))
    )
    (net (code "68") (name "Net-(LED43-K)") (class "Default")
      (node (ref "LED43") (pin "2") (pinfunction "K_2") (pintype "unspecified"))
      (node (ref "R60") (pin "2") (pinfunction "2_2") (pintype "input"))
    )
    (net (code "69") (name "Net-(LED44-K)") (class "Default")
      (node (ref "LED44") (pin "2") (pinfunction "K_2") (pintype "unspecified"))
      (node (ref "R61") (pin "2") (pinfunction "2_2") (pintype "input"))
    )
    (net (code "70") (name "Net-(LED45-K)") (class "Default")
      (node (ref "LED45") (pin "2") (pinfunction "K_2") (pintype "unspecified"))
      (node (ref "R62") (pin "2") (pinfunction "2_2") (pintype "input"))
    )
    (net (code "71") (name "Net-(LED46-K)") (class "Default")
      (node (ref "LED46") (pin "2") (pinfunction "K_2") (pintype "unspecified"))
      (node (ref "R63") (pin "2") (pinfunction "2_2") (pintype "input"))
    )
    (net (code "72") (name "VCC+5V") (class "Default")
      (node (ref "C13") (pin "2") (pinfunction "2_2") (pintype "input"))
      (node (ref "C5") (pin "2") (pinfunction "2_2") (pintype "input"))
      (node (ref "POWER") (pin "4") (pinfunction "4_4") (pintype "unspecified"))
      (node (ref "USB1") (pin "1") (pinfunction "VCC_1") (pintype "unspecified"))
    )
    (net (code "73") (name "unconnected-(U4-ALE{slash}P4.5-Pad27)") (class "Default")
      (node (ref "U4") (pin "27") (pinfunction "ALE/P4.5_27") (pintype "unspecified+no_connect"))
    )
    (net (code "74") (name "unconnected-(U4-EA#{slash}P4.6-Pad29)") (class "Default")
      (node (ref "U4") (pin "29") (pinfunction "EA#/P4.6_29") (pintype "unspecified+no_connect"))
    )
    (net (code "75") (name "unconnected-(U4-P4.1-Pad28)") (class "Default")
      (node (ref "U4") (pin "28") (pinfunction "P4.1_28") (pintype "unspecified+no_connect"))
    )
    (net (code "76") (name "unconnected-(U4-P4.2{slash}INT3#-Pad39)") (class "Default")
      (node (ref "U4") (pin "39") (pinfunction "P4.2/INT3#_39") (pintype "unspecified+no_connect"))
    )
    (net (code "77") (name "unconnected-(U4-P4.3{slash}INT2#-Pad6)") (class "Default")
      (node (ref "U4") (pin "6") (pinfunction "P4.3/INT2#_6") (pintype "unspecified+no_connect"))
    )
    (net (code "78") (name "unconnected-(U4-PSEN#{slash}P4.4-Pad26)") (class "Default")
      (node (ref "U4") (pin "26") (pinfunction "PSEN#/P4.4_26") (pintype "unspecified+no_connect"))
    )
  )
)
